# SoundPlayer.net
KiCad netlist of a schematic drawn in EAGLE
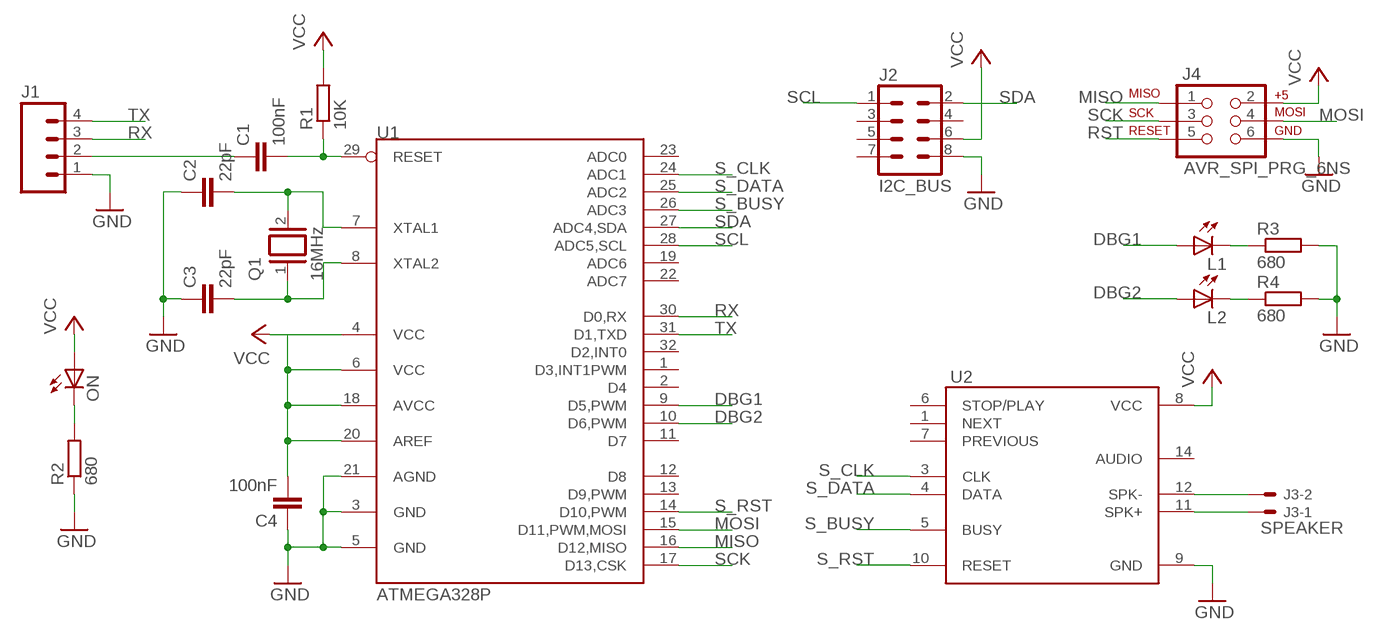
[diagram p0: schematic, sheet 1]

(export (version "E")
  (design (tool "Eeschema 10.0.6"))
  (components
    (comp (ref "C1")
      (value "100nF")
      (footprint "eagle-import:C0805")
      (libsource (lib "eagle-import") (part "C-EUC0805"))
    )
    (comp (ref "C2")
      (value "22pF")
      (footprint "eagle-import:C0805")
      (libsource (lib "eagle-import") (part "C-EUC0805"))
    )
    (comp (ref "C3")
      (value "22pF")
      (footprint "eagle-import:C0805")
      (libsource (lib "eagle-import") (part "C-EUC0805"))
    )
    (comp (ref "C4")
      (value "100nF")
      (footprint "eagle-import:C0805")
      (libsource (lib "eagle-import") (part "C-EUC0805"))
    )
    (comp (ref "J1")
      (value "M04PTH")
      (footprint "eagle-import:1X04")
      (libsource (lib "eagle-import") (part "M04PTH"))
    )
    (comp (ref "J2")
      (value "I2C_BUS")
      (footprint "eagle-import:SOCKET04X2_ANGLE")
      (libsource (lib "eagle-import") (part "IDC-SOCKET04X2IDC_SOCKECT04X2_ANGLE"))
    )
    (comp (ref "J3")
      (value "SPEAKER")
      (footprint "eagle-import:7395-02")
      (libsource (lib "eagle-import") (part "22-?-0205-7028"))
    )
    (comp (ref "J4")
      (value "AVR_SPI_PRG_6NS")
      (footprint "eagle-import:2X3-NS")
      (libsource (lib "eagle-import") (part "AVR_SPI_PRG_6NS"))
    )
    (comp (ref "L1")
      (value "LEDCHIPLED_0805")
      (footprint "eagle-import:CHIPLED_0805")
      (libsource (lib "eagle-import") (part "LEDCHIPLED_0805"))
    )
    (comp (ref "L2")
      (value "LEDCHIPLED_0805")
      (footprint "eagle-import:CHIPLED_0805")
      (libsource (lib "eagle-import") (part "LEDCHIPLED_0805"))
    )
    (comp (ref "ON")
      (value "LEDCHIPLED_0805")
      (footprint "eagle-import:CHIPLED_0805")
      (libsource (lib "eagle-import") (part "LEDCHIPLED_0805"))
    )
    (comp (ref "Q1")
      (value "16MHz")
      (footprint "eagle-import:QS")
      (libsource (lib "eagle-import") (part "XTAL/S"))
    )
    (comp (ref "R1")
      (value "10K")
      (footprint "eagle-import:R0805")
      (libsource (lib "eagle-import") (part "R-EU_R0805"))
    )
    (comp (ref "R2")
      (value "680")
      (footprint "eagle-import:R0805")
      (libsource (lib "eagle-import") (part "R-EU_R0805"))
    )
    (comp (ref "R3")
      (value "680")
      (footprint "eagle-import:R0805")
      (libsource (lib "eagle-import") (part "R-EU_R0805"))
    )
    (comp (ref "R4")
      (value "680")
      (footprint "eagle-import:R0805")
      (libsource (lib "eagle-import") (part "R-EU_R0805"))
    )
    (comp (ref "U1")
      (value "ATMEGA328P")
      (footprint "eagle-import:TQFP32-08")
      (libsource (lib "eagle-import") (part "ATMEGA328-SMT"))
    )
    (comp (ref "U2")
      (value "SOMO-14D")
      (footprint "eagle-import:SOMO-14D")
      (libsource (lib "eagle-import") (part "SOMO-14D"))
    )
  )
  (nets
    (net (code "1") (name "/DBG1") (class "Default")
      (node (ref "L1") (pin "A") (pinfunction "A_A") (pintype "passive"))
      (node (ref "U1") (pin "9") (pinfunction "D5,PWM_9") (pintype "bidirectional"))
    )
    (net (code "2") (name "/DBG2") (class "Default")
      (node (ref "L2") (pin "A") (pinfunction "A_A") (pintype "passive"))
      (node (ref "U1") (pin "10") (pinfunction "D6,PWM_10") (pintype "bidirectional"))
    )
    (net (code "3") (name "/MISO") (class "Default")
      (node (ref "J4") (pin "1") (pinfunction "1_1") (pintype "passive"))
      (node (ref "U1") (pin "16") (pinfunction "D12,MISO_16") (pintype "bidirectional"))
    )
    (net (code "4") (name "/MOSI") (class "Default")
      (node (ref "J4") (pin "4") (pinfunction "4_4") (pintype "passive"))
      (node (ref "U1") (pin "15") (pinfunction "D11,PWM,MOSI_15") (pintype "bidirectional"))
    )
    (net (code "5") (name "/RST") (class "Default")
      (node (ref "C1") (pin "2") (pinfunction "2_2") (pintype "passive"))
      (node (ref "J4") (pin "5") (pinfunction "5_5") (pintype "passive"))
      (node (ref "R1") (pin "1") (pinfunction "1_1") (pintype "passive"))
      (node (ref "U1") (pin "29") (pinfunction "RESET_29") (pintype "bidirectional"))
    )
    (net (code "6") (name "/RX") (class "Default")
      (node (ref "J1") (pin "3") (pinfunction "3_3") (pintype "passive"))
      (node (ref "U1") (pin "30") (pinfunction "D0,RX_30") (pintype "bidirectional"))
    )
    (net (code "7") (name "/SCK") (class "Default")
      (node (ref "J4") (pin "3") (pinfunction "3_3") (pintype "passive"))
      (node (ref "U1") (pin "17") (pinfunction "D13,CSK_17") (pintype "bidirectional"))
    )
    (net (code "8") (name "/SCL") (class "Default")
      (node (ref "J2") (pin "1") (pinfunction "1_1") (pintype "passive"))
      (node (ref "U1") (pin "28") (pinfunction "ADC5,SCL_28") (pintype "bidirectional"))
    )
    (net (code "9") (name "/SDA") (class "Default")
      (node (ref "J2") (pin "2") (pinfunction "2_2") (pintype "passive"))
      (node (ref "U1") (pin "27") (pinfunction "ADC4,SDA_27") (pintype "bidirectional"))
    )
    (net (code "10") (name "/S_BUSY") (class "Default")
      (node (ref "U1") (pin "26") (pinfunction "ADC3_26") (pintype "bidirectional"))
      (node (ref "U2") (pin "5") (pinfunction "BUSY_5") (pintype "bidirectional"))
    )
    (net (code "11") (name "/S_CLK") (class "Default")
      (node (ref "U1") (pin "24") (pinfunction "ADC1_24") (pintype "bidirectional"))
      (node (ref "U2") (pin "3") (pinfunction "CLK_3") (pintype "bidirectional"))
    )
    (net (code "12") (name "/S_DATA") (class "Default")
      (node (ref "U1") (pin "25") (pinfunction "ADC2_25") (pintype "bidirectional"))
      (node (ref "U2") (pin "4") (pinfunction "DATA_4") (pintype "bidirectional"))
    )
    (net (code "13") (name "/S_RST") (class "Default")
      (node (ref "U1") (pin "14") (pinfunction "D10,PWM_14") (pintype "bidirectional"))
      (node (ref "U2") (pin "10") (pinfunction "RESET_10") (pintype "bidirectional"))
    )
    (net (code "14") (name "/TX") (class "Default")
      (node (ref "J1") (pin "4") (pinfunction "4_4") (pintype "passive"))
      (node (ref "U1") (pin "31") (pinfunction "D1,TXD_31") (pintype "bidirectional"))
    )
    (net (code "15") (name "GND") (class "Default")
      (node (ref "C2") (pin "1") (pinfunction "1_1") (pintype "passive"))
      (node (ref "C3") (pin "1") (pinfunction "1_1") (pintype "passive"))
      (node (ref "C4") (pin "1") (pinfunction "1_1") (pintype "passive"))
      (node (ref "J1") (pin "1") (pinfunction "1_1") (pintype "passive"))
      (node (ref "J2") (pin "8") (pinfunction "8_8") (pintype "passive"))
      (node (ref "J4") (pin "6") (pinfunction "6_6") (pintype "passive"))
      (node (ref "R2") (pin "1") (pinfunction "1_1") (pintype "passive"))
      (node (ref "R3") (pin "2") (pinfunction "2_2") (pintype "passive"))
      (node (ref "R4") (pin "2") (pinfunction "2_2") (pintype "passive"))
      (node (ref "U1") (pin "21") (pinfunction "AGND_21") (pintype "bidirectional"))
      (node (ref "U1") (pin "3") (pinfunction "GND_3") (pintype "bidirectional"))
      (node (ref "U1") (pin "5") (pinfunction "GND_5") (pintype "bidirectional"))
      (node (ref "U2") (pin "9") (pinfunction "GND_9") (pintype "bidirectional"))
    )
    (net (code "16") (name "Net-(C1-Pad1)") (class "Default")
      (node (ref "C1") (pin "1") (pinfunction "1_1") (pintype "passive"))
      (node (ref "J1") (pin "2") (pinfunction "2_2") (pintype "passive"))
    )
    (net (code "17") (name "Net-(J3A-S)") (class "Default")
      (node (ref "J3") (pin "1") (pinfunction "S_1") (pintype "passive"))
      (node (ref "U2") (pin "11") (pinfunction "SPK+_11") (pintype "bidirectional"))
    )
    (net (code "18") (name "Net-(J3B-S)") (class "Default")
      (node (ref "J3") (pin "2") (pinfunction "S_2") (pintype "passive"))
      (node (ref "U2") (pin "12") (pinfunction "SPK-_12") (pintype "bidirectional"))
    )
    (net (code "19") (name "Net-(L1-PadC)") (class "Default")
      (node (ref "L1") (pin "C") (pinfunction "C_C") (pintype "passive"))
      (node (ref "R3") (pin "1") (pinfunction "1_1") (pintype "passive"))
    )
    (net (code "20") (name "Net-(L2-PadC)") (class "Default")
      (node (ref "L2") (pin "C") (pinfunction "C_C") (pintype "passive"))
      (node (ref "R4") (pin "1") (pinfunction "1_1") (pintype "passive"))
    )
    (net (code "21") (name "Net-(ON-PadC)") (class "Default")
      (node (ref "ON") (pin "C") (pinfunction "C_C") (pintype "passive"))
      (node (ref "R2") (pin "2") (pinfunction "2_2") (pintype "passive"))
    )
    (net (code "22") (name "Net-(U1-XTAL1)") (class "Default")
      (node (ref "C2") (pin "2") (pinfunction "2_2") (pintype "passive"))
      (node (ref "Q1") (pin "2") (pinfunction "2_2") (pintype "passive"))
      (node (ref "U1") (pin "7") (pinfunction "XTAL1_7") (pintype "bidirectional"))
    )
    (net (code "23") (name "Net-(U1-XTAL2)") (class "Default")
      (node (ref "C3") (pin "2") (pinfunction "2_2") (pintype "passive"))
      (node (ref "Q1") (pin "1") (pinfunction "1_1") (pintype "passive"))
      (node (ref "U1") (pin "8") (pinfunction "XTAL2_8") (pintype "bidirectional"))
    )
    (net (code "24") (name "VCC") (class "Default")
      (node (ref "C4") (pin "2") (pinfunction "2_2") (pintype "passive"))
      (node (ref "J2") (pin "6") (pinfunction "6_6") (pintype "passive"))
      (node (ref "J4") (pin "2") (pinfunction "2_2") (pintype "passive"))
      (node (ref "ON") (pin "A") (pinfunction "A_A") (pintype "passive"))
      (node (ref "R1") (pin "2") (pinfunction "2_2") (pintype "passive"))
      (node (ref "U1") (pin "18") (pinfunction "AVCC_18") (pintype "bidirectional"))
      (node (ref "U1") (pin "20") (pinfunction "AREF_20") (pintype "bidirectional"))
      (node (ref "U1") (pin "4") (pinfunction "VCC_4") (pintype "bidirectional"))
      (node (ref "U1") (pin "6") (pinfunction "VCC_6") (pintype "bidirectional"))
      (node (ref "U2") (pin "8") (pinfunction "VCC_8") (pintype "bidirectional"))
    )
    (net (code "25") (name "unconnected-(J2-Pad3)") (class "Default")
      (node (ref "J2") (pin "3") (pinfunction "3_3") (pintype "passive"))
    )
    (net (code "26") (name "unconnected-(J2-Pad4)") (class "Default")
      (node (ref "J2") (pin "4") (pinfunction "4_4") (pintype "passive"))
    )
    (net (code "27") (name "unconnected-(J2-Pad5)") (class "Default")
      (node (ref "J2") (pin "5") (pinfunction "5_5") (pintype "passive"))
    )
    (net (code "28") (name "unconnected-(J2-Pad7)") (class "Default")
      (node (ref "J2") (pin "7") (pinfunction "7_7") (pintype "passive"))
    )
    (net (code "29") (name "unconnected-(U1-ADC0-Pad23)") (class "Default")
      (node (ref "U1") (pin "23") (pinfunction "ADC0_23") (pintype "bidirectional"))
    )
    (net (code "30") (name "unconnected-(U1-ADC6-Pad19)") (class "Default")
      (node (ref "U1") (pin "19") (pinfunction "ADC6_19") (pintype "bidirectional"))
    )
    (net (code "31") (name "unconnected-(U1-ADC7-Pad22)") (class "Default")
      (node (ref "U1") (pin "22") (pinfunction "ADC7_22") (pintype "bidirectional"))
    )
    (net (code "32") (name "unconnected-(U1-D2,INT0-Pad32)") (class "Default")
      (node (ref "U1") (pin "32") (pinfunction "D2,INT0_32") (pintype "bidirectional"))
    )
    (net (code "33") (name "unconnected-(U1-D3,INT1PWM-Pad1)") (class "Default")
      (node (ref "U1") (pin "1") (pinfunction "D3,INT1PWM_1") (pintype "bidirectional"))
    )
    (net (code "34") (name "unconnected-(U1-D4-Pad2)") (class "Default")
      (node (ref "U1") (pin "2") (pinfunction "D4_2") (pintype "bidirectional"))
    )
    (net (code "35") (name "unconnected-(U1-D7-Pad11)") (class "Default")
      (node (ref "U1") (pin "11") (pinfunction "D7_11") (pintype "bidirectional"))
    )
    (net (code "36") (name "unconnected-(U1-D8-Pad12)") (class "Default")
      (node (ref "U1") (pin "12") (pinfunction "D8_12") (pintype "bidirectional"))
    )
    (net (code "37") (name "unconnected-(U1-D9,PWM-Pad13)") (class "Default")
      (node (ref "U1") (pin "13") (pinfunction "D9,PWM_13") (pintype "bidirectional"))
    )
    (net (code "38") (name "unconnected-(U2-AUDIO-Pad14)") (class "Default")
      (node (ref "U2") (pin "14") (pinfunction "AUDIO_14") (pintype "bidirectional"))
    )
    (net (code "39") (name "unconnected-(U2-NEXT-Pad1)") (class "Default")
      (node (ref "U2") (pin "1") (pinfunction "NEXT_1") (pintype "bidirectional"))
    )
    (net (code "40") (name "unconnected-(U2-PREVIOUS-Pad7)") (class "Default")
      (node (ref "U2") (pin "7") (pinfunction "PREVIOUS_7") (pintype "bidirectional"))
    )
    (net (code "41") (name "unconnected-(U2-STOP{slash}PLAY-Pad6)") (class "Default")
      (node (ref "U2") (pin "6") (pinfunction "STOP/PLAY_6") (pintype "bidirectional"))
    )
  )
)
